# CPLD_CLK_V2_0.net
KiCad netlist of a schematic drawn in Altium Designer
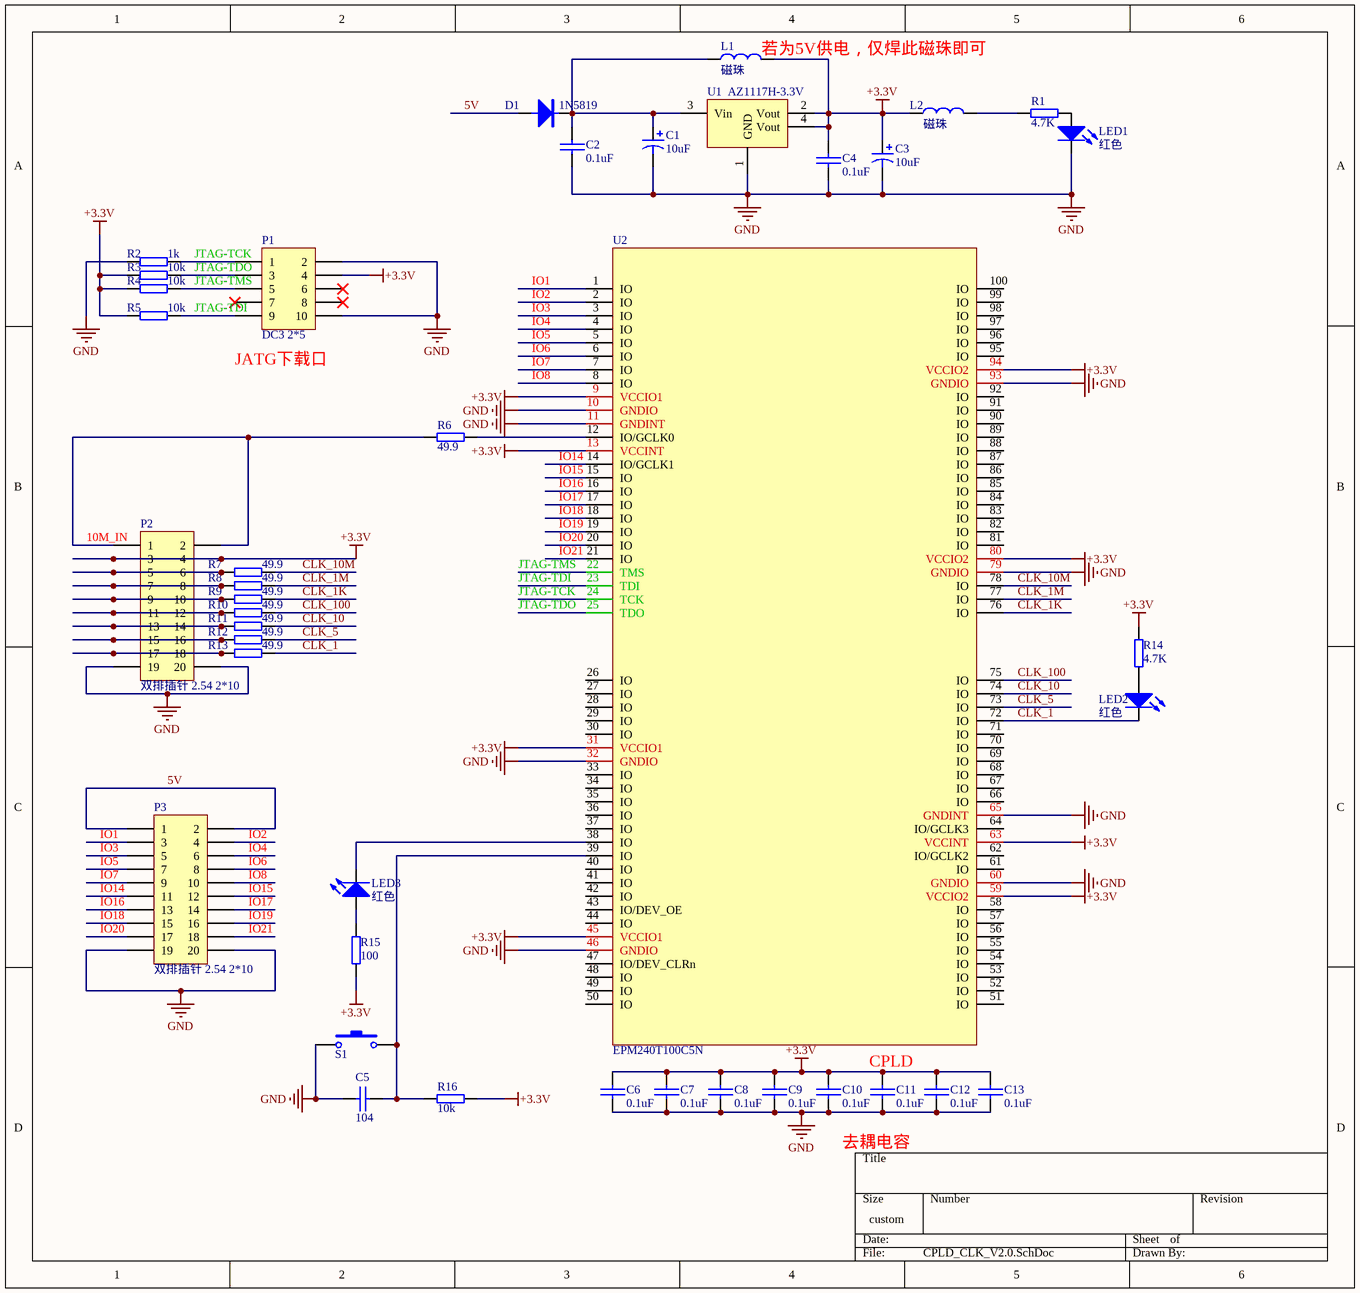
[diagram p0: CPLD_CLK_V2.0.SchDoc]

(export (version "E")
  (design (tool "Eeschema 10.0.6"))
  (components
    (comp (ref "C1")
      (value "10uF")
      (footprint "1206")
      (description "Polarized Capacitor (Radial)")
      (fields (field (name "PUBLISHER") "Altium Limited"))
      (libsource (lib "Miscellaneous Devices") (part "Cap Pol1"))
    )
    (comp (ref "C2")
      (value "0.1uF")
      (footprint "0805")
      (libsource (lib "Sch_Device_veryaz") (part "电容 贴片 0805"))
    )
    (comp (ref "C3")
      (value "10uF")
      (footprint "1206")
      (description "Polarized Capacitor (Radial)")
      (fields (field (name "PUBLISHER") "Altium Limited"))
      (libsource (lib "Miscellaneous Devices") (part "Cap Pol1"))
    )
    (comp (ref "C4")
      (value "0.1uF")
      (footprint "0805")
      (libsource (lib "Sch_Device_veryaz") (part "电容 贴片 0805"))
    )
    (comp (ref "C5")
      (value "104")
      (footprint "0805")
      (libsource (lib "Sch_Device_veryaz") (part "电容 贴片 0805"))
    )
    (comp (ref "C6")
      (value "0.1uF")
      (footprint "0805")
      (libsource (lib "Sch_Device_veryaz") (part "电容 贴片 0805"))
    )
    (comp (ref "C7")
      (value "0.1uF")
      (footprint "0805")
      (libsource (lib "Sch_Device_veryaz") (part "电容 贴片 0805"))
    )
    (comp (ref "C8")
      (value "0.1uF")
      (footprint "0805")
      (libsource (lib "Sch_Device_veryaz") (part "电容 贴片 0805"))
    )
    (comp (ref "C9")
      (value "0.1uF")
      (footprint "0805")
      (libsource (lib "Sch_Device_veryaz") (part "电容 贴片 0805"))
    )
    (comp (ref "C10")
      (value "0.1uF")
      (footprint "0805")
      (libsource (lib "Sch_Device_veryaz") (part "电容 贴片 0805"))
    )
    (comp (ref "C11")
      (value "0.1uF")
      (footprint "0805")
      (libsource (lib "Sch_Device_veryaz") (part "电容 贴片 0805"))
    )
    (comp (ref "C12")
      (value "0.1uF")
      (footprint "0805")
      (libsource (lib "Sch_Device_veryaz") (part "电容 贴片 0805"))
    )
    (comp (ref "C13")
      (value "0.1uF")
      (footprint "0805")
      (libsource (lib "Sch_Device_veryaz") (part "电容 贴片 0805"))
    )
    (comp (ref "D1")
      (value "1N5819")
      (footprint "二极管 贴片 2010")
      (libsource (lib "Sch_Device_veryaz") (part "二极管 1N5822"))
    )
    (comp (ref "L1") (value "磁珠") (footprint "0805") (libsource (lib "Sch_Device_veryaz") (part "磁珠")))
    (comp (ref "L2") (value "磁珠") (footprint "0805") (libsource (lib "Sch_Device_veryaz") (part "磁珠")))
    (comp (ref "LED1")
      (value "红色")
      (footprint "LED0805")
      (libsource (lib "Sch_Device_veryaz") (part "二极管 贴片发光 0805"))
    )
    (comp (ref "LED2")
      (value "红色")
      (footprint "LED0805")
      (libsource (lib "Sch_Device_veryaz") (part "二极管 贴片发光 0805"))
    )
    (comp (ref "LED3")
      (value "红色")
      (footprint "LED0805")
      (libsource (lib "Sch_Device_veryaz") (part "二极管 贴片发光 0805"))
    )
    (comp (ref "P1")
      (value "DC3压线座")
      (footprint "双排插针 2.54 2*5")
      (fields (field (name "封装") "DC3 2*5"))
      (libsource (lib "Sch_Device_veryaz") (part "联结件 DC3 2*5"))
    )
    (comp (ref "P2")
      (value "双排插针2.54 2*10")
      (footprint "双排插针 2.54 2*10")
      (fields (field (name "封装") "双排插针 2.54 2*10"))
      (libsource (lib "Sch_Device_veryaz") (part "联结件 双排插针 2.54 2*10"))
    )
    (comp (ref "P3")
      (value "双排插针2.54 2*10")
      (footprint "双排插针 2.54 2*10")
      (fields (field (name "封装") "双排插针 2.54 2*10"))
      (libsource (lib "Sch_Device_veryaz") (part "联结件 双排插针 2.54 2*10"))
    )
    (comp (ref "R1") (value "4.7K") (footprint "0805") (libsource (lib "") (part "电阻 贴片 0805_1")))
    (comp (ref "R2") (value "1k") (footprint "0805") (libsource (lib "") (part "电阻 贴片 0805_1")))
    (comp (ref "R3") (value "10k") (footprint "0805") (libsource (lib "") (part "电阻 贴片 0805_2")))
    (comp (ref "R4") (value "10k") (footprint "0805") (libsource (lib "") (part "电阻 贴片 0805_2")))
    (comp (ref "R5") (value "10k") (footprint "0805") (libsource (lib "") (part "电阻 贴片 0805_1")))
    (comp (ref "R6")
      (value "49.9")
      (footprint "0805")
      (libsource (lib "Sch_Device_veryaz") (part "电阻 贴片 0805"))
    )
    (comp (ref "R7")
      (value "49.9")
      (footprint "0805")
      (libsource (lib "Sch_Device_veryaz") (part "电阻 贴片 0805"))
    )
    (comp (ref "R8")
      (value "49.9")
      (footprint "0805")
      (libsource (lib "Sch_Device_veryaz") (part "电阻 贴片 0805"))
    )
    (comp (ref "R9")
      (value "49.9")
      (footprint "0805")
      (libsource (lib "Sch_Device_veryaz") (part "电阻 贴片 0805"))
    )
    (comp (ref "R10")
      (value "49.9")
      (footprint "0805")
      (libsource (lib "Sch_Device_veryaz") (part "电阻 贴片 0805"))
    )
    (comp (ref "R11")
      (value "49.9")
      (footprint "0805")
      (libsource (lib "Sch_Device_veryaz") (part "电阻 贴片 0805"))
    )
    (comp (ref "R12")
      (value "49.9")
      (footprint "0805")
      (libsource (lib "Sch_Device_veryaz") (part "电阻 贴片 0805"))
    )
    (comp (ref "R13")
      (value "49.9")
      (footprint "0805")
      (libsource (lib "Sch_Device_veryaz") (part "电阻 贴片 0805"))
    )
    (comp (ref "R14") (value "4.7K") (footprint "0805") (libsource (lib "") (part "电阻 贴片 0805_3")))
    (comp (ref "R15") (value "100") (footprint "0805") (libsource (lib "") (part "电阻 贴片 0805_3")))
    (comp (ref "R16")
      (value "10k")
      (footprint "0805")
      (libsource (lib "Sch_Device_veryaz") (part "电阻 贴片 0805"))
    )
    (comp (ref "S1")
      (value "key")
      (footprint "按键 轻触  6*3")
      (libsource (lib "Sch_Device_veryaz") (part "按键 轻触 6*6"))
    )
    (comp (ref "U1")
      (value "AZ1117H-3.3V")
      (footprint "SOT223")
      (libsource (lib "Sch_Device_veryaz") (part "贴片芯片 SPX1117M3-5.0"))
    )
    (comp (ref "U2")
      (value "EPM240T100C5N")
      (footprint "TQFP100")
      (libsource (lib "EPM240T100C5") (part "EPM240T100C5N"))
    )
  )
  (nets
    (net (code "1") (name "+3.3V") (class "Default")
      (node (ref "C10") (pin "2") (pintype "passive"))
      (node (ref "C11") (pin "2") (pintype "passive"))
      (node (ref "C12") (pin "2") (pintype "passive"))
      (node (ref "C13") (pin "2") (pintype "passive"))
      (node (ref "C3") (pin "1") (pinfunction "1_1") (pintype "passive"))
      (node (ref "C4") (pin "2") (pintype "passive"))
      (node (ref "C6") (pin "2") (pintype "passive"))
      (node (ref "C7") (pin "2") (pintype "passive"))
      (node (ref "C8") (pin "2") (pintype "passive"))
      (node (ref "C9") (pin "2") (pintype "passive"))
      (node (ref "L1") (pin "2") (pinfunction "2_2") (pintype "passive"))
      (node (ref "L2") (pin "1") (pinfunction "1_1") (pintype "passive"))
      (node (ref "P1") (pin "4") (pinfunction "4_4") (pintype "passive"))
      (node (ref "P2") (pin "3") (pinfunction "3_3") (pintype "passive"))
      (node (ref "P2") (pin "4") (pinfunction "4_4") (pintype "passive"))
      (node (ref "R14") (pin "1") (pinfunction "1_1") (pintype "passive"))
      (node (ref "R15") (pin "2") (pinfunction "2_2") (pintype "passive"))
      (node (ref "R16") (pin "1") (pinfunction "1_1") (pintype "passive"))
      (node (ref "R3") (pin "1") (pinfunction "1_1") (pintype "passive"))
      (node (ref "R4") (pin "1") (pinfunction "1_1") (pintype "passive"))
      (node (ref "R5") (pin "2") (pinfunction "2_2") (pintype "passive"))
      (node (ref "U1") (pin "2") (pinfunction "Vout_2") (pintype "passive"))
      (node (ref "U1") (pin "4") (pinfunction "Vout_4") (pintype "passive"))
      (node (ref "U2") (pin "13") (pinfunction "VCCINT_13") (pintype "passive"))
      (node (ref "U2") (pin "31") (pinfunction "VCCIO1_31") (pintype "passive"))
      (node (ref "U2") (pin "45") (pinfunction "VCCIO1_45") (pintype "passive"))
      (node (ref "U2") (pin "59") (pinfunction "VCCIO2_59") (pintype "passive"))
      (node (ref "U2") (pin "63") (pinfunction "VCCINT_63") (pintype "passive"))
      (node (ref "U2") (pin "80") (pinfunction "VCCIO2_80") (pintype "passive"))
      (node (ref "U2") (pin "9") (pinfunction "VCCIO1_9") (pintype "passive"))
      (node (ref "U2") (pin "94") (pinfunction "VCCIO2_94") (pintype "passive"))
    )
    (net (code "2") (name "/5V") (class "Default")
      (node (ref "D1") (pin "1") (pinfunction "A_1") (pintype "passive"))
      (node (ref "P3") (pin "1") (pinfunction "1_1") (pintype "passive"))
      (node (ref "P3") (pin "2") (pinfunction "2_2") (pintype "passive"))
    )
    (net (code "3") (name "/10M_IN") (class "Default")
      (node (ref "P2") (pin "1") (pinfunction "1_1") (pintype "passive"))
      (node (ref "P2") (pin "2") (pinfunction "2_2") (pintype "passive"))
      (node (ref "R6") (pin "2") (pinfunction "2_2") (pintype "passive"))
    )
    (net (code "4") (name "/CLK_1") (class "Default")
      (node (ref "LED2") (pin "2") (pinfunction "K_2") (pintype "passive"))
      (node (ref "R13") (pin "1") (pinfunction "1_1") (pintype "passive"))
      (node (ref "U2") (pin "72") (pinfunction "IO_72") (pintype "passive"))
    )
    (net (code "5") (name "/CLK_1K") (class "Default")
      (node (ref "R9") (pin "1") (pinfunction "1_1") (pintype "passive"))
      (node (ref "U2") (pin "76") (pinfunction "IO_76") (pintype "passive"))
    )
    (net (code "6") (name "/CLK_1M") (class "Default")
      (node (ref "R8") (pin "1") (pinfunction "1_1") (pintype "passive"))
      (node (ref "U2") (pin "77") (pinfunction "IO_77") (pintype "passive"))
    )
    (net (code "7") (name "/CLK_5") (class "Default")
      (node (ref "R12") (pin "1") (pinfunction "1_1") (pintype "passive"))
      (node (ref "U2") (pin "73") (pinfunction "IO_73") (pintype "passive"))
    )
    (net (code "8") (name "/CLK_10") (class "Default")
      (node (ref "R11") (pin "1") (pinfunction "1_1") (pintype "passive"))
      (node (ref "U2") (pin "74") (pinfunction "IO_74") (pintype "passive"))
    )
    (net (code "9") (name "/CLK_10M") (class "Default")
      (node (ref "R7") (pin "1") (pinfunction "1_1") (pintype "passive"))
      (node (ref "U2") (pin "78") (pinfunction "IO_78") (pintype "passive"))
    )
    (net (code "10") (name "/CLK_100") (class "Default")
      (node (ref "R10") (pin "1") (pinfunction "1_1") (pintype "passive"))
      (node (ref "U2") (pin "75") (pinfunction "IO_75") (pintype "passive"))
    )
    (net (code "11") (name "/IO1") (class "Default")
      (node (ref "P3") (pin "3") (pinfunction "3_3") (pintype "passive"))
      (node (ref "U2") (pin "1") (pinfunction "IO_1") (pintype "passive"))
    )
    (net (code "12") (name "/IO2") (class "Default")
      (node (ref "P3") (pin "4") (pinfunction "4_4") (pintype "passive"))
      (node (ref "U2") (pin "2") (pinfunction "IO_2") (pintype "passive"))
    )
    (net (code "13") (name "/IO3") (class "Default")
      (node (ref "P3") (pin "5") (pinfunction "5_5") (pintype "passive"))
      (node (ref "U2") (pin "3") (pinfunction "IO_3") (pintype "passive"))
    )
    (net (code "14") (name "/IO4") (class "Default")
      (node (ref "P3") (pin "6") (pinfunction "6_6") (pintype "passive"))
      (node (ref "U2") (pin "4") (pinfunction "IO_4") (pintype "passive"))
    )
    (net (code "15") (name "/IO5") (class "Default")
      (node (ref "P3") (pin "7") (pinfunction "7_7") (pintype "passive"))
      (node (ref "U2") (pin "5") (pinfunction "IO_5") (pintype "passive"))
    )
    (net (code "16") (name "/IO6") (class "Default")
      (node (ref "P3") (pin "8") (pinfunction "8_8") (pintype "passive"))
      (node (ref "U2") (pin "6") (pinfunction "IO_6") (pintype "passive"))
    )
    (net (code "17") (name "/IO7") (class "Default")
      (node (ref "P3") (pin "9") (pinfunction "9_9") (pintype "passive"))
      (node (ref "U2") (pin "7") (pinfunction "IO_7") (pintype "passive"))
    )
    (net (code "18") (name "/IO8") (class "Default")
      (node (ref "P3") (pin "10") (pinfunction "10_10") (pintype "passive"))
      (node (ref "U2") (pin "8") (pinfunction "IO_8") (pintype "passive"))
    )
    (net (code "19") (name "/IO14") (class "Default")
      (node (ref "P3") (pin "11") (pinfunction "11_11") (pintype "passive"))
      (node (ref "U2") (pin "14") (pinfunction "IO/GCLK1_14") (pintype "passive"))
    )
    (net (code "20") (name "/IO15") (class "Default")
      (node (ref "P3") (pin "12") (pinfunction "12_12") (pintype "passive"))
      (node (ref "U2") (pin "15") (pinfunction "IO_15") (pintype "passive"))
    )
    (net (code "21") (name "/IO16") (class "Default")
      (node (ref "P3") (pin "13") (pinfunction "13_13") (pintype "passive"))
      (node (ref "U2") (pin "16") (pinfunction "IO_16") (pintype "passive"))
    )
    (net (code "22") (name "/IO17") (class "Default")
      (node (ref "P3") (pin "14") (pinfunction "14_14") (pintype "passive"))
      (node (ref "U2") (pin "17") (pinfunction "IO_17") (pintype "passive"))
    )
    (net (code "23") (name "/IO18") (class "Default")
      (node (ref "P3") (pin "15") (pinfunction "15_15") (pintype "passive"))
      (node (ref "U2") (pin "18") (pinfunction "IO_18") (pintype "passive"))
    )
    (net (code "24") (name "/IO19") (class "Default")
      (node (ref "P3") (pin "16") (pinfunction "16_16") (pintype "passive"))
      (node (ref "U2") (pin "19") (pinfunction "IO_19") (pintype "passive"))
    )
    (net (code "25") (name "/IO20") (class "Default")
      (node (ref "P3") (pin "17") (pinfunction "17_17") (pintype "passive"))
      (node (ref "U2") (pin "20") (pinfunction "IO_20") (pintype "passive"))
    )
    (net (code "26") (name "/IO21") (class "Default")
      (node (ref "P3") (pin "18") (pinfunction "18_18") (pintype "passive"))
      (node (ref "U2") (pin "21") (pinfunction "IO_21") (pintype "passive"))
    )
    (net (code "27") (name "/JTAG-TCK") (class "Default")
      (node (ref "P1") (pin "1") (pinfunction "1_1") (pintype "passive"))
      (node (ref "R2") (pin "1") (pinfunction "1_1") (pintype "passive"))
      (node (ref "U2") (pin "24") (pinfunction "TCK_24") (pintype "passive"))
    )
    (net (code "28") (name "/JTAG-TDI") (class "Default")
      (node (ref "P1") (pin "9") (pinfunction "9_9") (pintype "passive"))
      (node (ref "R5") (pin "1") (pinfunction "1_1") (pintype "passive"))
      (node (ref "U2") (pin "23") (pinfunction "TDI_23") (pintype "passive"))
    )
    (net (code "29") (name "/JTAG-TDO") (class "Default")
      (node (ref "P1") (pin "3") (pinfunction "3_3") (pintype "passive"))
      (node (ref "R3") (pin "2") (pinfunction "2_2") (pintype "passive"))
      (node (ref "U2") (pin "25") (pinfunction "TDO_25") (pintype "passive"))
    )
    (net (code "30") (name "/JTAG-TMS") (class "Default")
      (node (ref "P1") (pin "5") (pinfunction "5_5") (pintype "passive"))
      (node (ref "R4") (pin "2") (pinfunction "2_2") (pintype "passive"))
      (node (ref "U2") (pin "22") (pinfunction "TMS_22") (pintype "passive"))
    )
    (net (code "31") (name "GND") (class "Default")
      (node (ref "C1") (pin "2") (pinfunction "2_2") (pintype "passive"))
      (node (ref "C10") (pin "1") (pintype "passive"))
      (node (ref "C11") (pin "1") (pintype "passive"))
      (node (ref "C12") (pin "1") (pintype "passive"))
      (node (ref "C13") (pin "1") (pintype "passive"))
      (node (ref "C2") (pin "1") (pintype "passive"))
      (node (ref "C3") (pin "2") (pinfunction "2_2") (pintype "passive"))
      (node (ref "C4") (pin "1") (pintype "passive"))
      (node (ref "C5") (pin "1") (pintype "passive"))
      (node (ref "C6") (pin "1") (pintype "passive"))
      (node (ref "C7") (pin "1") (pintype "passive"))
      (node (ref "C8") (pin "1") (pintype "passive"))
      (node (ref "C9") (pin "1") (pintype "passive"))
      (node (ref "LED1") (pin "2") (pinfunction "K_2") (pintype "passive"))
      (node (ref "P1") (pin "10") (pinfunction "10_10") (pintype "passive"))
      (node (ref "P1") (pin "2") (pinfunction "2_2") (pintype "passive"))
      (node (ref "P2") (pin "19") (pinfunction "19_19") (pintype "passive"))
      (node (ref "P2") (pin "20") (pinfunction "20_20") (pintype "passive"))
      (node (ref "P3") (pin "19") (pinfunction "19_19") (pintype "passive"))
      (node (ref "P3") (pin "20") (pinfunction "20_20") (pintype "passive"))
      (node (ref "R2") (pin "2") (pinfunction "2_2") (pintype "passive"))
      (node (ref "S1") (pin "1") (pinfunction "1_1") (pintype "passive"))
      (node (ref "U1") (pin "1") (pinfunction "GND_1") (pintype "passive"))
      (node (ref "U2") (pin "10") (pinfunction "GNDIO_10") (pintype "passive"))
      (node (ref "U2") (pin "11") (pinfunction "GNDINT_11") (pintype "passive"))
      (node (ref "U2") (pin "32") (pinfunction "GNDIO_32") (pintype "passive"))
      (node (ref "U2") (pin "46") (pinfunction "GNDIO_46") (pintype "passive"))
      (node (ref "U2") (pin "60") (pinfunction "GNDIO_60") (pintype "passive"))
      (node (ref "U2") (pin "65") (pinfunction "GNDINT_65") (pintype "passive"))
      (node (ref "U2") (pin "79") (pinfunction "GNDIO_79") (pintype "passive"))
      (node (ref "U2") (pin "93") (pinfunction "GNDIO_93") (pintype "passive"))
    )
    (net (code "32") (name "Net-(C5-Pad2)") (class "Default")
      (node (ref "C5") (pin "2") (pintype "passive"))
      (node (ref "R16") (pin "2") (pinfunction "2_2") (pintype "passive"))
      (node (ref "S1") (pin "2") (pinfunction "2_2") (pintype "passive"))
      (node (ref "U2") (pin "39") (pinfunction "IO_39") (pintype "passive"))
    )
    (net (code "33") (name "Net-(D1-K)") (class "Default")
      (node (ref "C1") (pin "1") (pinfunction "1_1") (pintype "passive"))
      (node (ref "C2") (pin "2") (pintype "passive"))
      (node (ref "D1") (pin "2") (pinfunction "K_2") (pintype "passive"))
      (node (ref "L1") (pin "1") (pinfunction "1_1") (pintype "passive"))
      (node (ref "U1") (pin "3") (pinfunction "Vin_3") (pintype "passive"))
    )
    (net (code "34") (name "Net-(L2-Pad2)") (class "Default")
      (node (ref "L2") (pin "2") (pinfunction "2_2") (pintype "passive"))
      (node (ref "R1") (pin "2") (pinfunction "2_2") (pintype "passive"))
    )
    (net (code "35") (name "Net-(LED1-A)") (class "Default")
      (node (ref "LED1") (pin "1") (pinfunction "A_1") (pintype "passive"))
      (node (ref "R1") (pin "1") (pinfunction "1_1") (pintype "passive"))
    )
    (net (code "36") (name "Net-(LED2-A)") (class "Default")
      (node (ref "LED2") (pin "1") (pinfunction "A_1") (pintype "passive"))
      (node (ref "R14") (pin "2") (pinfunction "2_2") (pintype "passive"))
    )
    (net (code "37") (name "Net-(LED3-A)") (class "Default")
      (node (ref "LED3") (pin "1") (pinfunction "A_1") (pintype "passive"))
      (node (ref "R15") (pin "1") (pinfunction "1_1") (pintype "passive"))
    )
    (net (code "38") (name "Net-(LED3-K)") (class "Default")
      (node (ref "LED3") (pin "2") (pinfunction "K_2") (pintype "passive"))
      (node (ref "U2") (pin "38") (pinfunction "IO_38") (pintype "passive"))
    )
    (net (code "39") (name "Net-(P2-Pad5)") (class "Default")
      (node (ref "P2") (pin "5") (pinfunction "5_5") (pintype "passive"))
      (node (ref "P2") (pin "6") (pinfunction "6_6") (pintype "passive"))
      (node (ref "R7") (pin "2") (pinfunction "2_2") (pintype "passive"))
    )
    (net (code "40") (name "Net-(P2-Pad7)") (class "Default")
      (node (ref "P2") (pin "7") (pinfunction "7_7") (pintype "passive"))
      (node (ref "P2") (pin "8") (pinfunction "8_8") (pintype "passive"))
      (node (ref "R8") (pin "2") (pinfunction "2_2") (pintype "passive"))
    )
    (net (code "41") (name "Net-(P2-Pad10)") (class "Default")
      (node (ref "P2") (pin "10") (pinfunction "10_10") (pintype "passive"))
      (node (ref "P2") (pin "9") (pinfunction "9_9") (pintype "passive"))
      (node (ref "R9") (pin "2") (pinfunction "2_2") (pintype "passive"))
    )
    (net (code "42") (name "Net-(P2-Pad11)") (class "Default")
      (node (ref "P2") (pin "11") (pinfunction "11_11") (pintype "passive"))
      (node (ref "P2") (pin "12") (pinfunction "12_12") (pintype "passive"))
      (node (ref "R10") (pin "2") (pinfunction "2_2") (pintype "passive"))
    )
    (net (code "43") (name "Net-(P2-Pad13)") (class "Default")
      (node (ref "P2") (pin "13") (pinfunction "13_13") (pintype "passive"))
      (node (ref "P2") (pin "14") (pinfunction "14_14") (pintype "passive"))
      (node (ref "R11") (pin "2") (pinfunction "2_2") (pintype "passive"))
    )
    (net (code "44") (name "Net-(P2-Pad15)") (class "Default")
      (node (ref "P2") (pin "15") (pinfunction "15_15") (pintype "passive"))
      (node (ref "P2") (pin "16") (pinfunction "16_16") (pintype "passive"))
      (node (ref "R12") (pin "2") (pinfunction "2_2") (pintype "passive"))
    )
    (net (code "45") (name "Net-(P2-Pad17)") (class "Default")
      (node (ref "P2") (pin "17") (pinfunction "17_17") (pintype "passive"))
      (node (ref "P2") (pin "18") (pinfunction "18_18") (pintype "passive"))
      (node (ref "R13") (pin "2") (pinfunction "2_2") (pintype "passive"))
    )
    (net (code "46") (name "Net-(U2-IO{slash}GCLK0)") (class "Default")
      (node (ref "R6") (pin "1") (pinfunction "1_1") (pintype "passive"))
      (node (ref "U2") (pin "12") (pinfunction "IO/GCLK0_12") (pintype "passive"))
    )
    (net (code "47") (name "unconnected-(P1-Pad6)") (class "Default")
      (node (ref "P1") (pin "6") (pinfunction "6_6") (pintype "passive+no_connect"))
    )
    (net (code "48") (name "unconnected-(P1-Pad7)") (class "Default")
      (node (ref "P1") (pin "7") (pinfunction "7_7") (pintype "passive+no_connect"))
    )
    (net (code "49") (name "unconnected-(P1-Pad8)") (class "Default")
      (node (ref "P1") (pin "8") (pinfunction "8_8") (pintype "passive+no_connect"))
    )
    (net (code "50") (name "unconnected-(U2-IO-Pad26)") (class "Default")
      (node (ref "U2") (pin "26") (pinfunction "IO_26") (pintype "passive"))
    )
    (net (code "51") (name "unconnected-(U2-IO-Pad27)") (class "Default")
      (node (ref "U2") (pin "27") (pinfunction "IO_27") (pintype "passive"))
    )
    (net (code "52") (name "unconnected-(U2-IO-Pad28)") (class "Default")
      (node (ref "U2") (pin "28") (pinfunction "IO_28") (pintype "passive"))
    )
    (net (code "53") (name "unconnected-(U2-IO-Pad29)") (class "Default")
      (node (ref "U2") (pin "29") (pinfunction "IO_29") (pintype "passive"))
    )
    (net (code "54") (name "unconnected-(U2-IO-Pad30)") (class "Default")
      (node (ref "U2") (pin "30") (pinfunction "IO_30") (pintype "passive"))
    )
    (net (code "55") (name "unconnected-(U2-IO-Pad33)") (class "Default")
      (node (ref "U2") (pin "33") (pinfunction "IO_33") (pintype "passive"))
    )
    (net (code "56") (name "unconnected-(U2-IO-Pad34)") (class "Default")
      (node (ref "U2") (pin "34") (pinfunction "IO_34") (pintype "passive"))
    )
    (net (code "57") (name "unconnected-(U2-IO-Pad35)") (class "Default")
      (node (ref "U2") (pin "35") (pinfunction "IO_35") (pintype "passive"))
    )
    (net (code "58") (name "unconnected-(U2-IO-Pad36)") (class "Default")
      (node (ref "U2") (pin "36") (pinfunction "IO_36") (pintype "passive"))
    )
    (net (code "59") (name "unconnected-(U2-IO-Pad37)") (class "Default")
      (node (ref "U2") (pin "37") (pinfunction "IO_37") (pintype "passive"))
    )
    (net (code "60") (name "unconnected-(U2-IO-Pad40)") (class "Default")
      (node (ref "U2") (pin "40") (pinfunction "IO_40") (pintype "passive"))
    )
    (net (code "61") (name "unconnected-(U2-IO-Pad41)") (class "Default")
      (node (ref "U2") (pin "41") (pinfunction "IO_41") (pintype "passive"))
    )
    (net (code "62") (name "unconnected-(U2-IO-Pad42)") (class "Default")
      (node (ref "U2") (pin "42") (pinfunction "IO_42") (pintype "passive"))
    )
    (net (code "63") (name "unconnected-(U2-IO-Pad44)") (class "Default")
      (node (ref "U2") (pin "44") (pinfunction "IO_44") (pintype "passive"))
    )
    (net (code "64") (name "unconnected-(U2-IO-Pad48)") (class "Default")
      (node (ref "U2") (pin "48") (pinfunction "IO_48") (pintype "passive"))
    )
    (net (code "65") (name "unconnected-(U2-IO-Pad49)") (class "Default")
      (node (ref "U2") (pin "49") (pinfunction "IO_49") (pintype "passive"))
    )
    (net (code "66") (name "unconnected-(U2-IO-Pad50)") (class "Default")
      (node (ref "U2") (pin "50") (pinfunction "IO_50") (pintype "passive"))
    )
    (net (code "67") (name "unconnected-(U2-IO-Pad51)") (class "Default")
      (node (ref "U2") (pin "51") (pinfunction "IO_51") (pintype "passive"))
    )
    (net (code "68") (name "unconnected-(U2-IO-Pad52)") (class "Default")
      (node (ref "U2") (pin "52") (pinfunction "IO_52") (pintype "passive"))
    )
    (net (code "69") (name "unconnected-(U2-IO-Pad53)") (class "Default")
      (node (ref "U2") (pin "53") (pinfunction "IO_53") (pintype "passive"))
    )
    (net (code "70") (name "unconnected-(U2-IO-Pad54)") (class "Default")
      (node (ref "U2") (pin "54") (pinfunction "IO_54") (pintype "passive"))
    )
    (net (code "71") (name "unconnected-(U2-IO-Pad55)") (class "Default")
      (node (ref "U2") (pin "55") (pinfunction "IO_55") (pintype "passive"))
    )
    (net (code "72") (name "unconnected-(U2-IO-Pad56)") (class "Default")
      (node (ref "U2") (pin "56") (pinfunction "IO_56") (pintype "passive"))
    )
    (net (code "73") (name "unconnected-(U2-IO-Pad57)") (class "Default")
      (node (ref "U2") (pin "57") (pinfunction "IO_57") (pintype "passive"))
    )
    (net (code "74") (name "unconnected-(U2-IO-Pad58)") (class "Default")
      (node (ref "U2") (pin "58") (pinfunction "IO_58") (pintype "passive"))
    )
    (net (code "75") (name "unconnected-(U2-IO-Pad61)") (class "Default")
      (node (ref "U2") (pin "61") (pinfunction "IO_61") (pintype "passive"))
    )
    (net (code "76") (name "unconnected-(U2-IO-Pad66)") (class "Default")
      (node (ref "U2") (pin "66") (pinfunction "IO_66") (pintype "passive"))
    )
    (net (code "77") (name "unconnected-(U2-IO-Pad67)") (class "Default")
      (node (ref "U2") (pin "67") (pinfunction "IO_67") (pintype "passive"))
    )
    (net (code "78") (name "unconnected-(U2-IO-Pad68)") (class "Default")
      (node (ref "U2") (pin "68") (pinfunction "IO_68") (pintype "passive"))
    )
    (net (code "79") (name "unconnected-(U2-IO-Pad69)") (class "Default")
      (node (ref "U2") (pin "69") (pinfunction "IO_69") (pintype "passive"))
    )
    (net (code "80") (name "unconnected-(U2-IO-Pad70)") (class "Default")
      (node (ref "U2") (pin "70") (pinfunction "IO_70") (pintype "passive"))
    )
    (net (code "81") (name "unconnected-(U2-IO-Pad71)") (class "Default")
      (node (ref "U2") (pin "71") (pinfunction "IO_71") (pintype "passive"))
    )
    (net (code "82") (name "unconnected-(U2-IO-Pad81)") (class "Default")
      (node (ref "U2") (pin "81") (pinfunction "IO_81") (pintype "passive"))
    )
    (net (code "83") (name "unconnected-(U2-IO-Pad82)") (class "Default")
      (node (ref "U2") (pin "82") (pinfunction "IO_82") (pintype "passive"))
    )
    (net (code "84") (name "unconnected-(U2-IO-Pad83)") (class "Default")
      (node (ref "U2") (pin "83") (pinfunction "IO_83") (pintype "passive"))
    )
    (net (code "85") (name "unconnected-(U2-IO-Pad84)") (class "Default")
      (node (ref "U2") (pin "84") (pinfunction "IO_84") (pintype "passive"))
    )
    (net (code "86") (name "unconnected-(U2-IO-Pad85)") (class "Default")
      (node (ref "U2") (pin "85") (pinfunction "IO_85") (pintype "passive"))
    )
    (net (code "87") (name "unconnected-(U2-IO-Pad86)") (class "Default")
      (node (ref "U2") (pin "86") (pinfunction "IO_86") (pintype "passive"))
    )
    (net (code "88") (name "unconnected-(U2-IO-Pad87)") (class "Default")
      (node (ref "U2") (pin "87") (pinfunction "IO_87") (pintype "passive"))
    )
    (net (code "89") (name "unconnected-(U2-IO-Pad88)") (class "Default")
      (node (ref "U2") (pin "88") (pinfunction "IO_88") (pintype "passive"))
    )
    (net (code "90") (name "unconnected-(U2-IO-Pad89)") (class "Default")
      (node (ref "U2") (pin "89") (pinfunction "IO_89") (pintype "passive"))
    )
    (net (code "91") (name "unconnected-(U2-IO-Pad90)") (class "Default")
      (node (ref "U2") (pin "90") (pinfunction "IO_90") (pintype "passive"))
    )
    (net (code "92") (name "unconnected-(U2-IO-Pad91)") (class "Default")
      (node (ref "U2") (pin "91") (pinfunction "IO_91") (pintype "passive"))
    )
    (net (code "93") (name "unconnected-(U2-IO-Pad92)") (class "Default")
      (node (ref "U2") (pin "92") (pinfunction "IO_92") (pintype "passive"))
    )
    (net (code "94") (name "unconnected-(U2-IO-Pad95)") (class "Default")
      (node (ref "U2") (pin "95") (pinfunction "IO_95") (pintype "passive"))
    )
    (net (code "95") (name "unconnected-(U2-IO-Pad96)") (class "Default")
      (node (ref "U2") (pin "96") (pinfunction "IO_96") (pintype "passive"))
    )
    (net (code "96") (name "unconnected-(U2-IO-Pad97)") (class "Default")
      (node (ref "U2") (pin "97") (pinfunction "IO_97") (pintype "passive"))
    )
    (net (code "97") (name "unconnected-(U2-IO-Pad98)") (class "Default")
      (node (ref "U2") (pin "98") (pinfunction "IO_98") (pintype "passive"))
    )
    (net (code "98") (name "unconnected-(U2-IO-Pad99)") (class "Default")
      (node (ref "U2") (pin "99") (pinfunction "IO_99") (pintype "passive"))
    )
    (net (code "99") (name "unconnected-(U2-IO-Pad100)") (class "Default")
      (node (ref "U2") (pin "100") (pinfunction "IO_100") (pintype "passive"))
    )
    (net (code "100") (name "unconnected-(U2-IO{slash}DEV_CLRn-Pad47)") (class "Default")
      (node (ref "U2") (pin "47") (pinfunction "IO/DEV_CLRn_47") (pintype "passive"))
    )
    (net (code "101") (name "unconnected-(U2-IO{slash}DEV_OE-Pad43)") (class "Default")
      (node (ref "U2") (pin "43") (pinfunction "IO/DEV_OE_43") (pintype "passive"))
    )
    (net (code "102") (name "unconnected-(U2-IO{slash}GCLK2-Pad62)") (class "Default")
      (node (ref "U2") (pin "62") (pinfunction "IO/GCLK2_62") (pintype "passive"))
    )
    (net (code "103") (name "unconnected-(U2-IO{slash}GCLK3-Pad64)") (class "Default")
      (node (ref "U2") (pin "64") (pinfunction "IO/GCLK3_64") (pintype "passive"))
    )
  )
)
